# morseSounder.net
KiCad netlist of a schematic drawn in EAGLE
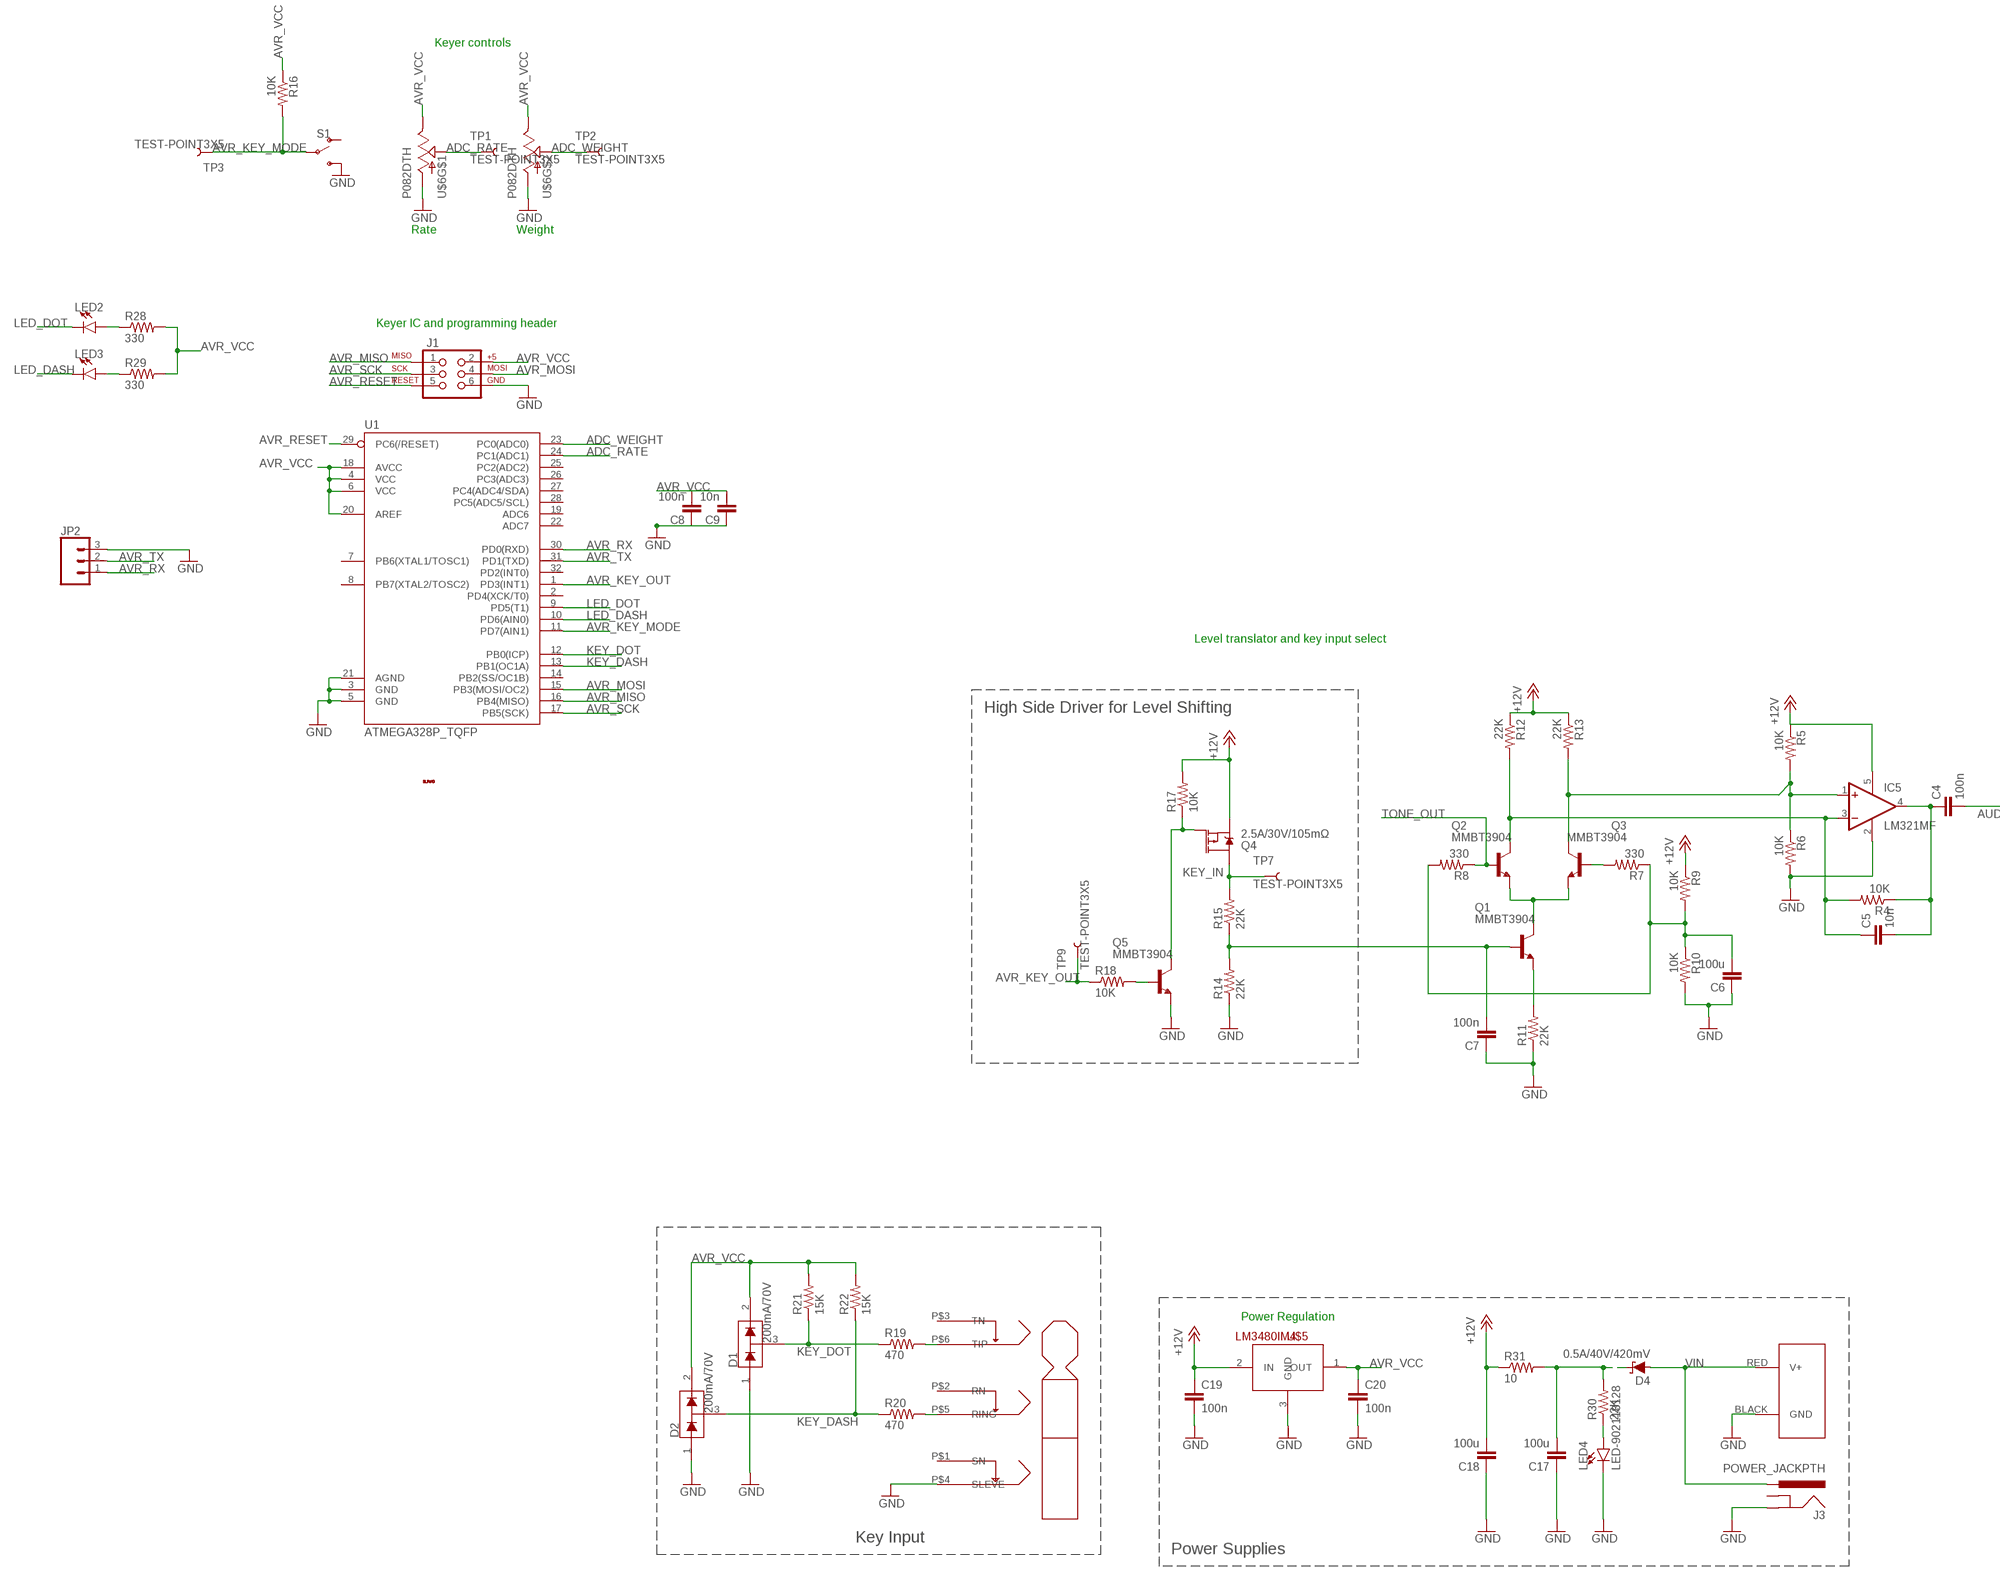
[diagram p0: schematic, sheet 1, part 1 of 2]
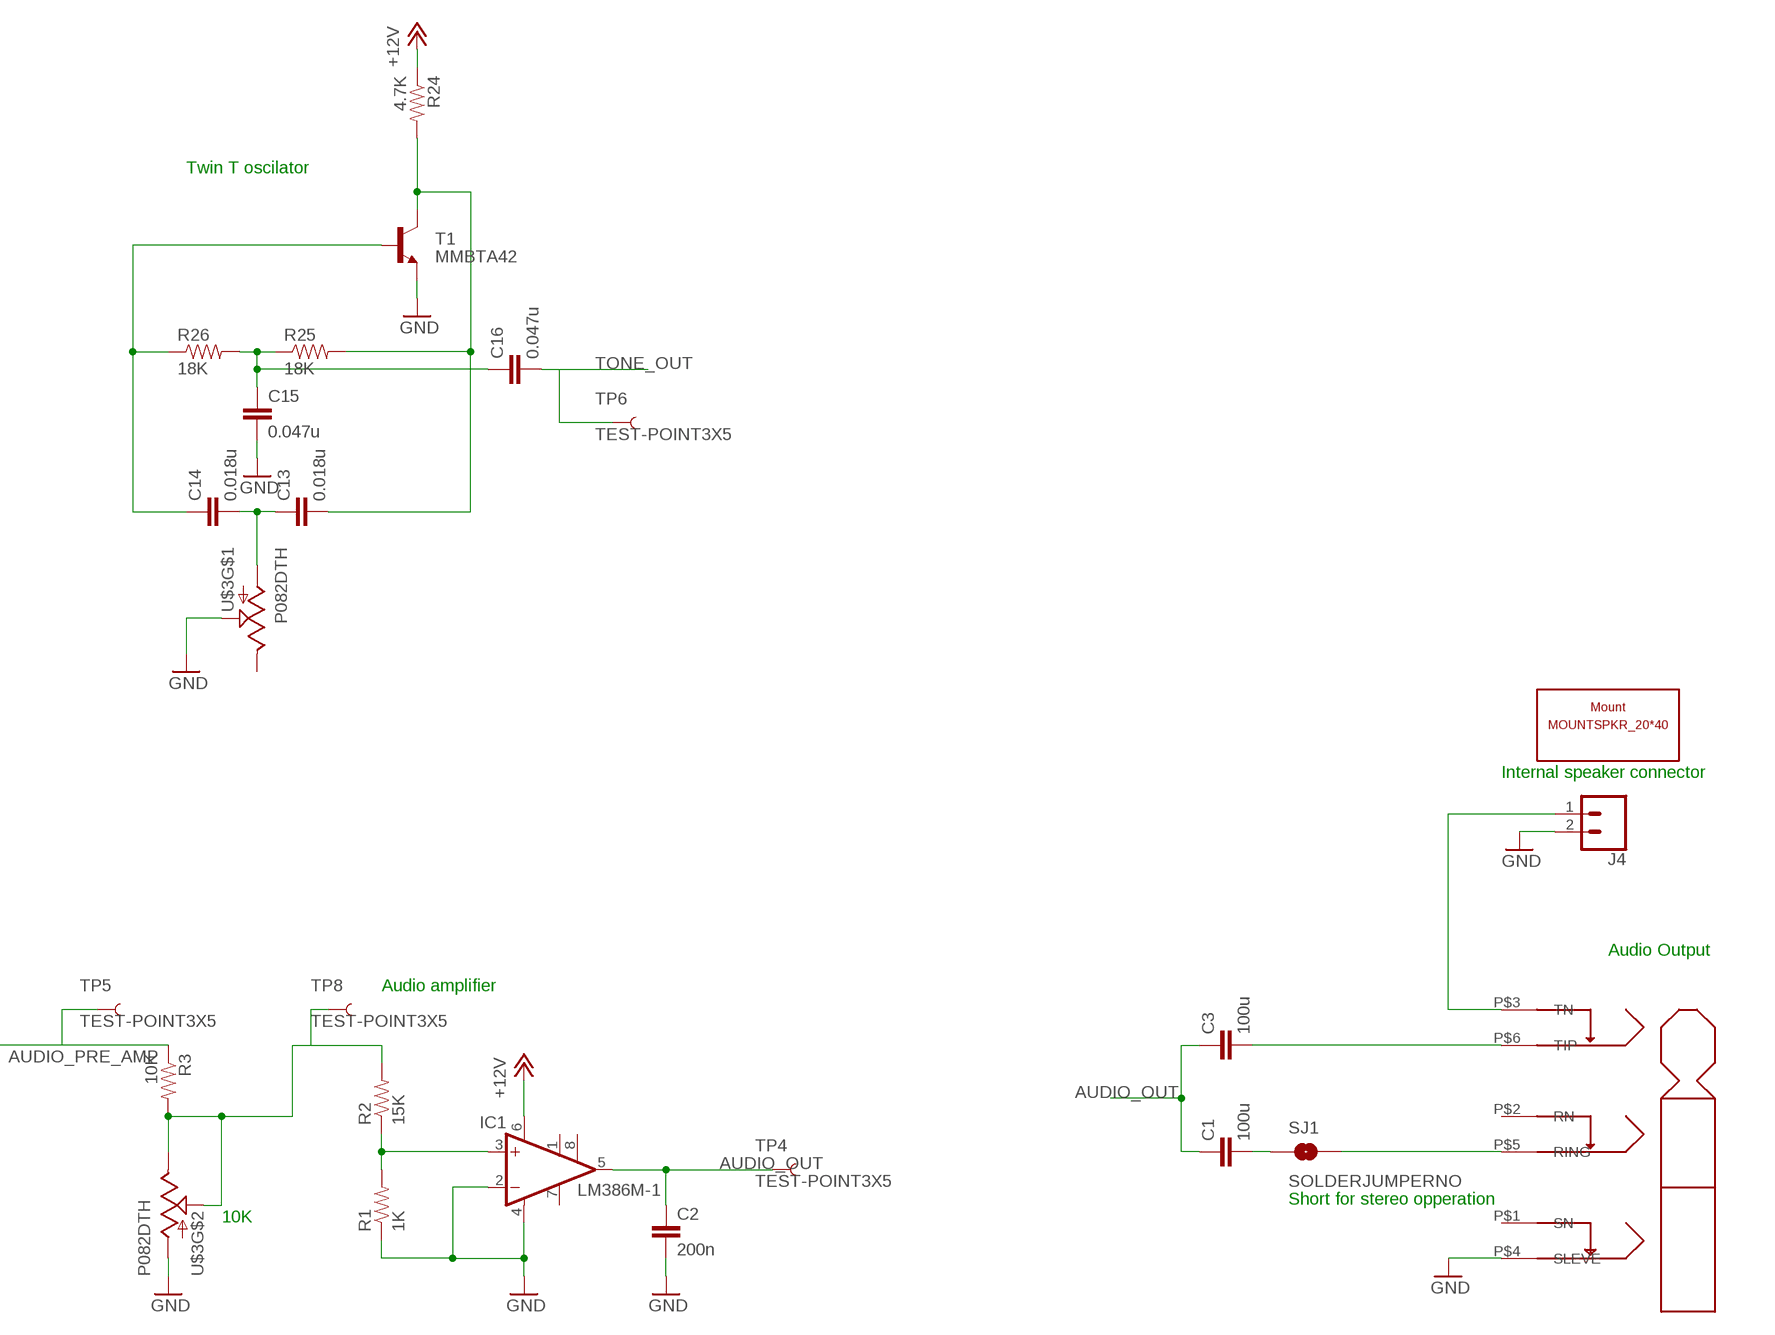
[diagram p1: schematic, sheet 1, part 2 of 2]

(export (version "E")
  (design (tool "Eeschema 10.0.6"))
  (components
    (comp (ref "C1")
      (value "100u")
      (footprint "eagle-import:0805")
      (libsource (lib "eagle-import") (part "CAP0805"))
    )
    (comp (ref "C2")
      (value "200n")
      (footprint "eagle-import:0805")
      (libsource (lib "eagle-import") (part "CAP0805"))
    )
    (comp (ref "C3")
      (value "100u")
      (footprint "eagle-import:0805")
      (libsource (lib "eagle-import") (part "CAP0805"))
    )
    (comp (ref "C4")
      (value "100n")
      (footprint "eagle-import:0805")
      (libsource (lib "eagle-import") (part "CAP0805"))
    )
    (comp (ref "C5")
      (value "10n")
      (footprint "eagle-import:0805")
      (libsource (lib "eagle-import") (part "CAP0805"))
    )
    (comp (ref "C6")
      (value "100u")
      (footprint "eagle-import:0805")
      (libsource (lib "eagle-import") (part "CAP0805"))
    )
    (comp (ref "C7")
      (value "100n")
      (footprint "eagle-import:0805")
      (libsource (lib "eagle-import") (part "CAP0805"))
    )
    (comp (ref "C8")
      (value "100n")
      (footprint "eagle-import:0805")
      (libsource (lib "eagle-import") (part "CAP0805"))
    )
    (comp (ref "C9")
      (value "10n")
      (footprint "eagle-import:0805")
      (libsource (lib "eagle-import") (part "CAP0805"))
    )
    (comp (ref "C13")
      (value "0.018u")
      (footprint "eagle-import:0805")
      (libsource (lib "eagle-import") (part "CAP0805"))
    )
    (comp (ref "C14")
      (value "0.018u")
      (footprint "eagle-import:0805")
      (libsource (lib "eagle-import") (part "CAP0805"))
    )
    (comp (ref "C15")
      (value "0.047u")
      (footprint "eagle-import:0805")
      (libsource (lib "eagle-import") (part "CAP0805"))
    )
    (comp (ref "C16")
      (value "0.047u")
      (footprint "eagle-import:0805")
      (libsource (lib "eagle-import") (part "CAP0805"))
    )
    (comp (ref "C17")
      (value "100u")
      (footprint "eagle-import:0805")
      (libsource (lib "eagle-import") (part "CAP0805"))
    )
    (comp (ref "C18")
      (value "100u")
      (footprint "eagle-import:0805")
      (libsource (lib "eagle-import") (part "CAP0805"))
    )
    (comp (ref "C19")
      (value "100n")
      (footprint "eagle-import:0805")
      (libsource (lib "eagle-import") (part "CAP0805"))
    )
    (comp (ref "C20")
      (value "100n")
      (footprint "eagle-import:0805")
      (libsource (lib "eagle-import") (part "CAP0805"))
    )
    (comp (ref "D1")
      (value "200mA/70V")
      (footprint "eagle-import:SOT23-3")
      (libsource (lib "eagle-import") (part "BAV99"))
    )
    (comp (ref "D2")
      (value "200mA/70V")
      (footprint "eagle-import:SOT23-3")
      (libsource (lib "eagle-import") (part "BAV99"))
    )
    (comp (ref "D4")
      (value "0.5A/40V/420mV")
      (footprint "eagle-import:SOD-323")
      (libsource (lib "eagle-import") (part "DIODE-SCHOTTKY-PMEG4005EJ"))
    )
    (comp (ref "IC1")
      (value "LM386M-1")
      (footprint "eagle-import:SO08")
      (libsource (lib "eagle-import") (part "LM386?-M1"))
    )
    (comp (ref "IC5")
      (value "LM321MF")
      (footprint "eagle-import:SOT23-5")
      (libsource (lib "eagle-import") (part "LM321?MF"))
    )
    (comp (ref "J1")
      (value "AVR_SPI_PRG_6PTH")
      (footprint "eagle-import:2X3")
      (libsource (lib "eagle-import") (part "AVR_SPI_PRG_6PTH"))
    )
    (comp (ref "J2")
      (value "POWERPOLE_POWER25A_HORIZONTAL_G2")
      (footprint "eagle-import:POWERPOLE_PAIR_25A_HORIZ_G2")
      (libsource (lib "eagle-import") (part "POWERPOLE_POWER25A_HORIZONTAL_G2"))
    )
    (comp (ref "J3")
      (value "POWER_JACKPTH")
      (footprint "eagle-import:POWER_JACK_PTH")
      (libsource (lib "eagle-import") (part "POWER_JACKPTH"))
    )
    (comp (ref "J4")
      (value "CONN_02")
      (footprint "eagle-import:1X02")
      (libsource (lib "eagle-import") (part "CONN_02"))
    )
    (comp (ref "JP2")
      (value "CONN_03")
      (footprint "eagle-import:1X03")
      (libsource (lib "eagle-import") (part "CONN_03"))
    )
    (comp (ref "LED2")
      (value "LED-RED1206")
      (footprint "eagle-import:LED-1206")
      (libsource (lib "eagle-import") (part "LED-RED1206"))
    )
    (comp (ref "LED3")
      (value "LED-RED1206")
      (footprint "eagle-import:LED-1206")
      (libsource (lib "eagle-import") (part "LED-RED1206"))
    )
    (comp (ref "LED4")
      (value "LED-902118128")
      (footprint "eagle-import:MULTICOMP-2118128")
      (libsource (lib "eagle-import") (part "LED-902118128"))
    )
    (comp (ref "Q1")
      (value "MMBT3904")
      (footprint "eagle-import:SOT23-BEC")
      (libsource (lib "eagle-import") (part "-NPN-SOT23-BECMMBT3904LT1"))
    )
    (comp (ref "Q2")
      (value "MMBT3904")
      (footprint "eagle-import:SOT23-BEC")
      (libsource (lib "eagle-import") (part "-NPN-SOT23-BECMMBT3904LT1"))
    )
    (comp (ref "Q3")
      (value "MMBT3904")
      (footprint "eagle-import:SOT23-BEC")
      (libsource (lib "eagle-import") (part "-NPN-SOT23-BECMMBT3904LT1"))
    )
    (comp (ref "Q4")
      (value "2.5A/30V/105mΩ")
      (footprint "eagle-import:SOT23-3")
      (libsource (lib "eagle-import") (part "MOSFET_PCH-DMG2307L"))
    )
    (comp (ref "Q5")
      (value "MMBT3904")
      (footprint "eagle-import:SOT23-BEC")
      (libsource (lib "eagle-import") (part "-NPN-SOT23-BECMMBT3904LT1"))
    )
    (comp (ref "R1")
      (value "1K")
      (footprint "eagle-import:0805")
      (libsource (lib "eagle-import") (part "RESISTOR0805-RES"))
    )
    (comp (ref "R2")
      (value "15K")
      (footprint "eagle-import:0805")
      (libsource (lib "eagle-import") (part "RESISTOR0805-RES"))
    )
    (comp (ref "R3")
      (value "10K")
      (footprint "eagle-import:0805")
      (libsource (lib "eagle-import") (part "RESISTOR0805-RES"))
    )
    (comp (ref "R4")
      (value "10K")
      (footprint "eagle-import:0805")
      (libsource (lib "eagle-import") (part "RESISTOR0805-RES"))
    )
    (comp (ref "R5")
      (value "10K")
      (footprint "eagle-import:0805")
      (libsource (lib "eagle-import") (part "RESISTOR0805-RES"))
    )
    (comp (ref "R6")
      (value "10K")
      (footprint "eagle-import:0805")
      (libsource (lib "eagle-import") (part "RESISTOR0805-RES"))
    )
    (comp (ref "R7")
      (value "330")
      (footprint "eagle-import:0805")
      (libsource (lib "eagle-import") (part "RESISTOR0805-RES"))
    )
    (comp (ref "R8")
      (value "330")
      (footprint "eagle-import:0805")
      (libsource (lib "eagle-import") (part "RESISTOR0805-RES"))
    )
    (comp (ref "R9")
      (value "10K")
      (footprint "eagle-import:0805")
      (libsource (lib "eagle-import") (part "RESISTOR0805-RES"))
    )
    (comp (ref "R10")
      (value "10K")
      (footprint "eagle-import:0805")
      (libsource (lib "eagle-import") (part "RESISTOR0805-RES"))
    )
    (comp (ref "R11")
      (value "22K")
      (footprint "eagle-import:0805")
      (libsource (lib "eagle-import") (part "RESISTOR0805-RES"))
    )
    (comp (ref "R12")
      (value "22K")
      (footprint "eagle-import:0805")
      (libsource (lib "eagle-import") (part "RESISTOR0805-RES"))
    )
    (comp (ref "R13")
      (value "22K")
      (footprint "eagle-import:0805")
      (libsource (lib "eagle-import") (part "RESISTOR0805-RES"))
    )
    (comp (ref "R14")
      (value "22K")
      (footprint "eagle-import:0805")
      (libsource (lib "eagle-import") (part "RESISTOR0805-RES"))
    )
    (comp (ref "R15")
      (value "22K")
      (footprint "eagle-import:0805")
      (libsource (lib "eagle-import") (part "RESISTOR0805-RES"))
    )
    (comp (ref "R16")
      (value "10K")
      (footprint "eagle-import:0805")
      (libsource (lib "eagle-import") (part "RESISTOR0805-RES"))
    )
    (comp (ref "R17")
      (value "10K")
      (footprint "eagle-import:0805")
      (libsource (lib "eagle-import") (part "RESISTOR0805-RES"))
    )
    (comp (ref "R18")
      (value "10K")
      (footprint "eagle-import:0805")
      (libsource (lib "eagle-import") (part "RESISTOR0805-RES"))
    )
    (comp (ref "R19")
      (value "470")
      (footprint "eagle-import:0805")
      (libsource (lib "eagle-import") (part "RESISTOR0805-RES"))
    )
    (comp (ref "R20")
      (value "470")
      (footprint "eagle-import:0805")
      (libsource (lib "eagle-import") (part "RESISTOR0805-RES"))
    )
    (comp (ref "R21")
      (value "15K")
      (footprint "eagle-import:0805")
      (libsource (lib "eagle-import") (part "RESISTOR0805-RES"))
    )
    (comp (ref "R22")
      (value "15K")
      (footprint "eagle-import:0805")
      (libsource (lib "eagle-import") (part "RESISTOR0805-RES"))
    )
    (comp (ref "R24")
      (value "4.7K")
      (footprint "eagle-import:0805")
      (libsource (lib "eagle-import") (part "RESISTOR0805-RES"))
    )
    (comp (ref "R25")
      (value "18K")
      (footprint "eagle-import:0805")
      (libsource (lib "eagle-import") (part "RESISTOR0805-RES"))
    )
    (comp (ref "R26")
      (value "18K")
      (footprint "eagle-import:0805")
      (libsource (lib "eagle-import") (part "RESISTOR0805-RES"))
    )
    (comp (ref "R28")
      (value "330")
      (footprint "eagle-import:0805")
      (libsource (lib "eagle-import") (part "RESISTOR0805-RES"))
    )
    (comp (ref "R29")
      (value "330")
      (footprint "eagle-import:0805")
      (libsource (lib "eagle-import") (part "RESISTOR0805-RES"))
    )
    (comp (ref "R30")
      (value "22K")
      (footprint "eagle-import:0805")
      (libsource (lib "eagle-import") (part "RESISTOR0805-RES"))
    )
    (comp (ref "R31")
      (value "10")
      (footprint "eagle-import:0805")
      (libsource (lib "eagle-import") (part "RESISTOR0805-RES"))
    )
    (comp (ref "S1")
      (value "SWITCH-SPDTTE-1825232-1")
      (footprint "eagle-import:TE-1825232-1")
      (libsource (lib "eagle-import") (part "SWITCH-SPDTTE-1825232-1"))
    )
    (comp (ref "SJ1")
      (value "SOLDERJUMPERNO")
      (footprint "eagle-import:SJ_2S-NO")
      (libsource (lib "eagle-import") (part "SOLDERJUMPERNO"))
    )
    (comp (ref "T1")
      (value "MMBTA42")
      (footprint "eagle-import:SOT23")
      (libsource (lib "eagle-import") (part "TRANSISTOR_NPNSOT23"))
    )
    (comp (ref "TP1")
      (value "TEST-POINT3X5")
      (footprint "eagle-import:PAD.03X.05")
      (libsource (lib "eagle-import") (part "TEST-POINT3X5"))
    )
    (comp (ref "TP2")
      (value "TEST-POINT3X5")
      (footprint "eagle-import:PAD.03X.05")
      (libsource (lib "eagle-import") (part "TEST-POINT3X5"))
    )
    (comp (ref "TP3")
      (value "TEST-POINT3X5")
      (footprint "eagle-import:PAD.03X.05")
      (libsource (lib "eagle-import") (part "TEST-POINT3X5"))
    )
    (comp (ref "TP4")
      (value "TEST-POINT3X5")
      (footprint "eagle-import:PAD.03X.05")
      (libsource (lib "eagle-import") (part "TEST-POINT3X5"))
    )
    (comp (ref "TP5")
      (value "TEST-POINT3X5")
      (footprint "eagle-import:PAD.03X.05")
      (libsource (lib "eagle-import") (part "TEST-POINT3X5"))
    )
    (comp (ref "TP6")
      (value "TEST-POINT3X5")
      (footprint "eagle-import:PAD.03X.05")
      (libsource (lib "eagle-import") (part "TEST-POINT3X5"))
    )
    (comp (ref "TP7")
      (value "TEST-POINT3X5")
      (footprint "eagle-import:PAD.03X.05")
      (libsource (lib "eagle-import") (part "TEST-POINT3X5"))
    )
    (comp (ref "TP8")
      (value "TEST-POINT3X5")
      (footprint "eagle-import:PAD.03X.05")
      (libsource (lib "eagle-import") (part "TEST-POINT3X5"))
    )
    (comp (ref "TP9")
      (value "TEST-POINT3X5")
      (footprint "eagle-import:PAD.03X.05")
      (libsource (lib "eagle-import") (part "TEST-POINT3X5"))
    )
    (comp (ref "U$1")
      (value "NRJ6HH")
      (footprint "eagle-import:NRJ6HH")
      (libsource (lib "eagle-import") (part "NRJ6HH"))
    )
    (comp (ref "U$2")
      (value "NRJ6HH")
      (footprint "eagle-import:NRJ6HH")
      (libsource (lib "eagle-import") (part "NRJ6HH"))
    )
    (comp (ref "U$3")
      (value "P082DTH")
      (footprint "eagle-import:P082D")
      (libsource (lib "eagle-import") (part "P082DTH"))
    )
    (comp (ref "U$4")
      (value "MOUNTSPKR_20*40")
      (footprint "eagle-import:SKR_MNT")
      (libsource (lib "eagle-import") (part "MOUNTSPKR_2040"))
    )
    (comp (ref "U$5")
      (value "LM3480IM4")
      (footprint "eagle-import:SOT23-3")
      (libsource (lib "eagle-import") (part "LM3480IM4"))
    )
    (comp (ref "U$6")
      (value "P082DTH")
      (footprint "eagle-import:P082D")
      (libsource (lib "eagle-import") (part "P082DTH"))
    )
    (comp (ref "U$7")
      (value "LOGO_SUWSLOGO_LARGE")
      (footprint "eagle-import:LOGO_SUWS")
      (libsource (lib "eagle-import") (part "LOGO_SUWSLOGO_LARGE"))
    )
    (comp (ref "U1")
      (value "ATMEGA328P_TQFP")
      (footprint "eagle-import:TQFP32-08")
      (libsource (lib "eagle-import") (part "ATMEGA328P_TQFP"))
    )
  )
  (nets
    (net (code "1") (name "+12V") (class "Default")
      (node (ref "C18") (pin "2") (pinfunction "2_2") (pintype "passive"))
      (node (ref "C19") (pin "1") (pinfunction "1_1") (pintype "passive"))
      (node (ref "IC1") (pin "6") (pinfunction "VS_6") (pintype "power_in"))
      (node (ref "IC5") (pin "5") (pinfunction "V+_5") (pintype "power_in"))
      (node (ref "Q4") (pin "2") (pinfunction "S_2") (pintype "bidirectional"))
      (node (ref "R12") (pin "1") (pinfunction "1_1") (pintype "passive"))
      (node (ref "R13") (pin "1") (pinfunction "1_1") (pintype "passive"))
      (node (ref "R17") (pin "2") (pinfunction "2_2") (pintype "passive"))
      (node (ref "R24") (pin "1") (pinfunction "1_1") (pintype "passive"))
      (node (ref "R31") (pin "1") (pinfunction "1_1") (pintype "passive"))
      (node (ref "R5") (pin "1") (pinfunction "1_1") (pintype "passive"))
      (node (ref "R9") (pin "1") (pinfunction "1_1") (pintype "passive"))
      (node (ref "U$5") (pin "2") (pinfunction "IN_2") (pintype "bidirectional"))
    )
    (net (code "2") (name "/ADC_RATE") (class "Default")
      (node (ref "TP1") (pin "P$1") (pinfunction "1_P$1") (pintype "bidirectional"))
      (node (ref "U$6") (pin "F2") (pinfunction "S_F2") (pintype "passive"))
      (node (ref "U1") (pin "24") (pinfunction "PC1(ADC1)_24") (pintype "bidirectional"))
    )
    (net (code "3") (name "/ADC_WEIGHT") (class "Default")
      (node (ref "TP2") (pin "P$1") (pinfunction "1_P$1") (pintype "bidirectional"))
      (node (ref "U$6") (pin "R2") (pinfunction "S_R2") (pintype "passive"))
      (node (ref "U1") (pin "23") (pinfunction "PC0(ADC0)_23") (pintype "bidirectional"))
    )
    (net (code "4") (name "/AUDIO_OUT") (class "Default")
      (node (ref "C1") (pin "1") (pinfunction "1_1") (pintype "passive"))
      (node (ref "C2") (pin "1") (pinfunction "1_1") (pintype "passive"))
      (node (ref "C3") (pin "1") (pinfunction "1_1") (pintype "passive"))
      (node (ref "IC1") (pin "5") (pinfunction "OUT_5") (pintype "output"))
      (node (ref "TP4") (pin "P$1") (pinfunction "1_P$1") (pintype "bidirectional"))
    )
    (net (code "5") (name "/AUDIO_PRE_AMP") (class "Default")
      (node (ref "C4") (pin "2") (pinfunction "2_2") (pintype "passive"))
      (node (ref "R3") (pin "1") (pinfunction "1_1") (pintype "passive"))
      (node (ref "TP5") (pin "P$1") (pinfunction "1_P$1") (pintype "bidirectional"))
    )
    (net (code "6") (name "/AVR_KEY_MODE") (class "Default")
      (node (ref "R16") (pin "2") (pinfunction "2_2") (pintype "passive"))
      (node (ref "S1") (pin "2") (pinfunction "P_2") (pintype "passive"))
      (node (ref "TP3") (pin "P$1") (pinfunction "1_P$1") (pintype "bidirectional"))
      (node (ref "U1") (pin "11") (pinfunction "PD7(AIN1)_11") (pintype "bidirectional"))
    )
    (net (code "7") (name "/AVR_KEY_OUT") (class "Default")
      (node (ref "R18") (pin "1") (pinfunction "1_1") (pintype "passive"))
      (node (ref "TP9") (pin "P$1") (pinfunction "1_P$1") (pintype "bidirectional"))
      (node (ref "U1") (pin "1") (pinfunction "PD3(INT1)_1") (pintype "bidirectional"))
    )
    (net (code "8") (name "/AVR_MISO") (class "Default")
      (node (ref "J1") (pin "1") (pinfunction "1_1") (pintype "passive"))
      (node (ref "U1") (pin "16") (pinfunction "PB4(MISO)_16") (pintype "bidirectional"))
    )
    (net (code "9") (name "/AVR_MOSI") (class "Default")
      (node (ref "J1") (pin "4") (pinfunction "4_4") (pintype "passive"))
      (node (ref "U1") (pin "15") (pinfunction "PB3(MOSI/OC2)_15") (pintype "bidirectional"))
    )
    (net (code "10") (name "/AVR_RESET") (class "Default")
      (node (ref "J1") (pin "5") (pinfunction "5_5") (pintype "passive"))
      (node (ref "U1") (pin "29") (pinfunction "PC6(/RESET)_29") (pintype "bidirectional"))
    )
    (net (code "11") (name "/AVR_RX") (class "Default")
      (node (ref "JP2") (pin "1") (pinfunction "1_1") (pintype "passive"))
      (node (ref "U1") (pin "30") (pinfunction "PD0(RXD)_30") (pintype "bidirectional"))
    )
    (net (code "12") (name "/AVR_SCK") (class "Default")
      (node (ref "J1") (pin "3") (pinfunction "3_3") (pintype "passive"))
      (node (ref "U1") (pin "17") (pinfunction "PB5(SCK)_17") (pintype "bidirectional"))
    )
    (net (code "13") (name "/AVR_TX") (class "Default")
      (node (ref "JP2") (pin "2") (pinfunction "2_2") (pintype "passive"))
      (node (ref "U1") (pin "31") (pinfunction "PD1(TXD)_31") (pintype "bidirectional"))
    )
    (net (code "14") (name "/AVR_VCC") (class "Default")
      (node (ref "C20") (pin "1") (pinfunction "1_1") (pintype "passive"))
      (node (ref "C8") (pin "2") (pinfunction "2_2") (pintype "passive"))
      (node (ref "C9") (pin "2") (pinfunction "2_2") (pintype "passive"))
      (node (ref "D1") (pin "2") (pinfunction "C2_2") (pintype "bidirectional"))
      (node (ref "D2") (pin "2") (pinfunction "C2_2") (pintype "bidirectional"))
      (node (ref "J1") (pin "2") (pinfunction "2_2") (pintype "passive"))
      (node (ref "R16") (pin "1") (pinfunction "1_1") (pintype "passive"))
      (node (ref "R21") (pin "2") (pinfunction "2_2") (pintype "passive"))
      (node (ref "R22") (pin "2") (pinfunction "2_2") (pintype "passive"))
      (node (ref "R28") (pin "2") (pinfunction "2_2") (pintype "passive"))
      (node (ref "R29") (pin "2") (pinfunction "2_2") (pintype "passive"))
      (node (ref "U$5") (pin "1") (pinfunction "OUT_1") (pintype "bidirectional"))
      (node (ref "U$6") (pin "F3") (pinfunction "E_F3") (pintype "passive"))
      (node (ref "U$6") (pin "R3") (pinfunction "E_R3") (pintype "passive"))
      (node (ref "U1") (pin "18") (pinfunction "AVCC_18") (pintype "bidirectional"))
      (node (ref "U1") (pin "20") (pinfunction "AREF_20") (pintype "bidirectional"))
      (node (ref "U1") (pin "4") (pinfunction "VCC_4") (pintype "bidirectional"))
      (node (ref "U1") (pin "6") (pinfunction "VCC_6") (pintype "bidirectional"))
    )
    (net (code "15") (name "/KEY_DASH") (class "Default")
      (node (ref "D2") (pin "3") (pinfunction "COM_3") (pintype "bidirectional"))
      (node (ref "R20") (pin "1") (pinfunction "1_1") (pintype "passive"))
      (node (ref "R22") (pin "1") (pinfunction "1_1") (pintype "passive"))
      (node (ref "U1") (pin "13") (pinfunction "PB1(OC1A)_13") (pintype "bidirectional"))
    )
    (net (code "16") (name "/KEY_DOT") (class "Default")
      (node (ref "D1") (pin "3") (pinfunction "COM_3") (pintype "bidirectional"))
      (node (ref "R19") (pin "1") (pinfunction "1_1") (pintype "passive"))
      (node (ref "R21") (pin "1") (pinfunction "1_1") (pintype "passive"))
      (node (ref "U1") (pin "12") (pinfunction "PB0(ICP)_12") (pintype "bidirectional"))
    )
    (net (code "17") (name "/KEY_IN") (class "Default")
      (node (ref "Q4") (pin "3") (pinfunction "D_3") (pintype "bidirectional"))
      (node (ref "R15") (pin "2") (pinfunction "2_2") (pintype "passive"))
      (node (ref "TP7") (pin "P$1") (pinfunction "1_P$1") (pintype "bidirectional"))
    )
    (net (code "18") (name "/LED_DASH") (class "Default")
      (node (ref "LED3") (pin "C") (pinfunction "C_C") (pintype "passive"))
      (node (ref "U1") (pin "10") (pinfunction "PD6(AIN0)_10") (pintype "bidirectional"))
    )
    (net (code "19") (name "/LED_DOT") (class "Default")
      (node (ref "LED2") (pin "C") (pinfunction "C_C") (pintype "passive"))
      (node (ref "U1") (pin "9") (pinfunction "PD5(T1)_9") (pintype "bidirectional"))
    )
    (net (code "20") (name "/TONE_OUT") (class "Default")
      (node (ref "C16") (pin "2") (pinfunction "2_2") (pintype "passive"))
      (node (ref "Q2") (pin "B") (pinfunction "B_B") (pintype "passive"))
      (node (ref "R8") (pin "1") (pinfunction "1_1") (pintype "passive"))
      (node (ref "TP6") (pin "P$1") (pinfunction "1_P$1") (pintype "bidirectional"))
    )
    (net (code "21") (name "/VIN") (class "Default")
      (node (ref "D4") (pin "A") (pinfunction "A_A") (pintype "passive"))
      (node (ref "J2") (pin "RED") (pinfunction "V+_RED") (pintype "power_in"))
      (node (ref "J3") (pin "PWR") (pinfunction "PWR_PWR") (pintype "bidirectional"))
    )
    (net (code "22") (name "GND") (class "Default")
      (node (ref "C15") (pin "2") (pinfunction "2_2") (pintype "passive"))
      (node (ref "C17") (pin "1") (pinfunction "1_1") (pintype "passive"))
      (node (ref "C18") (pin "1") (pinfunction "1_1") (pintype "passive"))
      (node (ref "C19") (pin "2") (pinfunction "2_2") (pintype "passive"))
      (node (ref "C2") (pin "2") (pinfunction "2_2") (pintype "passive"))
      (node (ref "C20") (pin "2") (pinfunction "2_2") (pintype "passive"))
      (node (ref "C6") (pin "1") (pinfunction "1_1") (pintype "passive"))
      (node (ref "C7") (pin "1") (pinfunction "1_1") (pintype "passive"))
      (node (ref "C8") (pin "1") (pinfunction "1_1") (pintype "passive"))
      (node (ref "C9") (pin "1") (pinfunction "1_1") (pintype "passive"))
      (node (ref "D1") (pin "1") (pinfunction "A1_1") (pintype "bidirectional"))
      (node (ref "D2") (pin "1") (pinfunction "A1_1") (pintype "bidirectional"))
      (node (ref "IC1") (pin "2") (pinfunction "-IN_2") (pintype "input"))
      (node (ref "IC1") (pin "4") (pinfunction "GND_4") (pintype "power_in"))
      (node (ref "IC5") (pin "2") (pinfunction "V-_2") (pintype "power_in"))
      (node (ref "J1") (pin "6") (pinfunction "6_6") (pintype "passive"))
      (node (ref "J2") (pin "BLACK") (pinfunction "GND_BLACK") (pintype "power_in"))
      (node (ref "J3") (pin "GND") (pinfunction "GND_GND") (pintype "bidirectional"))
      (node (ref "J4") (pin "2") (pinfunction "2_2") (pintype "passive"))
      (node (ref "JP2") (pin "3") (pinfunction "3_3") (pintype "passive"))
      (node (ref "LED4") (pin "P$2") (pinfunction "C_P$2") (pintype "passive"))
      (node (ref "Q5") (pin "E") (pinfunction "E_E") (pintype "passive"))
      (node (ref "R1") (pin "1") (pinfunction "1_1") (pintype "passive"))
      (node (ref "R10") (pin "2") (pinfunction "2_2") (pintype "passive"))
      (node (ref "R11") (pin "1") (pinfunction "1_1") (pintype "passive"))
      (node (ref "R14") (pin "1") (pinfunction "1_1") (pintype "passive"))
      (node (ref "R6") (pin "2") (pinfunction "2_2") (pintype "passive"))
      (node (ref "S1") (pin "3") (pinfunction "S_3") (pintype "passive"))
      (node (ref "T1") (pin "2") (pinfunction "E_2") (pintype "passive"))
      (node (ref "U$1") (pin "P$4") (pinfunction "SLEVE_P$4") (pintype "bidirectional"))
      (node (ref "U$2") (pin "P$4") (pinfunction "SLEVE_P$4") (pintype "bidirectional"))
      (node (ref "U$3") (pin "F2") (pinfunction "S_F2") (pintype "passive"))
      (node (ref "U$3") (pin "R1") (pinfunction "A_R1") (pintype "passive"))
      (node (ref "U$5") (pin "3") (pinfunction "GND_3") (pintype "bidirectional"))
      (node (ref "U$6") (pin "F1") (pinfunction "A_F1") (pintype "passive"))
      (node (ref "U$6") (pin "R1") (pinfunction "A_R1") (pintype "passive"))
      (node (ref "U1") (pin "21") (pinfunction "AGND_21") (pintype "bidirectional"))
      (node (ref "U1") (pin "3") (pinfunction "GND_3") (pintype "bidirectional"))
      (node (ref "U1") (pin "5") (pinfunction "GND_5") (pintype "bidirectional"))
    )
    (net (code "23") (name "Net-(C1-Pad2)") (class "Default")
      (node (ref "C1") (pin "2") (pinfunction "2_2") (pintype "passive"))
      (node (ref "SJ1") (pin "1") (pinfunction "1_1") (pintype "passive"))
    )
    (net (code "24") (name "Net-(C6-Pad2)") (class "Default")
      (node (ref "C6") (pin "2") (pinfunction "2_2") (pintype "passive"))
      (node (ref "R10") (pin "1") (pinfunction "1_1") (pintype "passive"))
      (node (ref "R7") (pin "1") (pinfunction "1_1") (pintype "passive"))
      (node (ref "R8") (pin "2") (pinfunction "2_2") (pintype "passive"))
      (node (ref "R9") (pin "2") (pinfunction "2_2") (pintype "passive"))
    )
    (net (code "25") (name "Net-(C7-Pad2)") (class "Default")
      (node (ref "C7") (pin "2") (pinfunction "2_2") (pintype "passive"))
      (node (ref "Q1") (pin "B") (pinfunction "B_B") (pintype "passive"))
      (node (ref "R14") (pin "2") (pinfunction "2_2") (pintype "passive"))
      (node (ref "R15") (pin "1") (pinfunction "1_1") (pintype "passive"))
    )
    (net (code "26") (name "Net-(C15-Pad1)") (class "Default")
      (node (ref "C15") (pin "1") (pinfunction "1_1") (pintype "passive"))
      (node (ref "C16") (pin "1") (pinfunction "1_1") (pintype "passive"))
      (node (ref "R25") (pin "1") (pinfunction "1_1") (pintype "passive"))
      (node (ref "R26") (pin "2") (pinfunction "2_2") (pintype "passive"))
    )
    (net (code "27") (name "Net-(C17-Pad2)") (class "Default")
      (node (ref "C17") (pin "2") (pinfunction "2_2") (pintype "passive"))
      (node (ref "D4") (pin "C") (pinfunction "C_C") (pintype "passive"))
      (node (ref "R30") (pin "2") (pinfunction "2_2") (pintype "passive"))
      (node (ref "R31") (pin "2") (pinfunction "2_2") (pintype "passive"))
    )
    (net (code "28") (name "Net-(IC1-+IN)") (class "Default")
      (node (ref "IC1") (pin "3") (pinfunction "+IN_3") (pintype "input"))
      (node (ref "R1") (pin "2") (pinfunction "2_2") (pintype "passive"))
      (node (ref "R2") (pin "1") (pinfunction "1_1") (pintype "passive"))
    )
    (net (code "29") (name "Net-(IC5-+IN)") (class "Default")
      (node (ref "IC5") (pin "1") (pinfunction "+IN_1") (pintype "input"))
      (node (ref "Q3") (pin "C") (pinfunction "C_C") (pintype "passive"))
      (node (ref "R13") (pin "2") (pinfunction "2_2") (pintype "passive"))
      (node (ref "R5") (pin "2") (pinfunction "2_2") (pintype "passive"))
      (node (ref "R6") (pin "1") (pinfunction "1_1") (pintype "passive"))
    )
    (net (code "30") (name "Net-(IC5--IN)") (class "Default")
      (node (ref "C5") (pin "1") (pinfunction "1_1") (pintype "passive"))
      (node (ref "IC5") (pin "3") (pinfunction "-IN_3") (pintype "input"))
      (node (ref "Q2") (pin "C") (pinfunction "C_C") (pintype "passive"))
      (node (ref "R12") (pin "2") (pinfunction "2_2") (pintype "passive"))
      (node (ref "R4") (pin "2") (pinfunction "2_2") (pintype "passive"))
    )
    (net (code "31") (name "Net-(IC5-OUT)") (class "Default")
      (node (ref "C4") (pin "1") (pinfunction "1_1") (pintype "passive"))
      (node (ref "C5") (pin "2") (pinfunction "2_2") (pintype "passive"))
      (node (ref "IC5") (pin "4") (pinfunction "OUT_4") (pintype "output"))
      (node (ref "R4") (pin "1") (pinfunction "1_1") (pintype "passive"))
    )
    (net (code "32") (name "Net-(LED2-PadA)") (class "Default")
      (node (ref "LED2") (pin "A") (pinfunction "A_A") (pintype "passive"))
      (node (ref "R28") (pin "1") (pinfunction "1_1") (pintype "passive"))
    )
    (net (code "33") (name "Net-(LED3-PadA)") (class "Default")
      (node (ref "LED3") (pin "A") (pinfunction "A_A") (pintype "passive"))
      (node (ref "R29") (pin "1") (pinfunction "1_1") (pintype "passive"))
    )
    (net (code "34") (name "Net-(LED4-A)") (class "Default")
      (node (ref "LED4") (pin "P$1") (pinfunction "A_P$1") (pintype "passive"))
      (node (ref "R30") (pin "1") (pinfunction "1_1") (pintype "passive"))
    )
    (net (code "35") (name "Net-(Q1-PadC)") (class "Default")
      (node (ref "Q1") (pin "C") (pinfunction "C_C") (pintype "passive"))
      (node (ref "Q2") (pin "E") (pinfunction "E_E") (pintype "passive"))
      (node (ref "Q3") (pin "E") (pinfunction "E_E") (pintype "passive"))
    )
    (net (code "36") (name "Net-(Q1-PadE)") (class "Default")
      (node (ref "Q1") (pin "E") (pinfunction "E_E") (pintype "passive"))
      (node (ref "R11") (pin "2") (pinfunction "2_2") (pintype "passive"))
    )
    (net (code "37") (name "Net-(Q3-PadB)") (class "Default")
      (node (ref "Q3") (pin "B") (pinfunction "B_B") (pintype "passive"))
      (node (ref "R7") (pin "2") (pinfunction "2_2") (pintype "passive"))
    )
    (net (code "38") (name "Net-(Q4-G)") (class "Default")
      (node (ref "Q4") (pin "1") (pinfunction "G_1") (pintype "bidirectional"))
      (node (ref "Q5") (pin "C") (pinfunction "C_C") (pintype "passive"))
      (node (ref "R17") (pin "1") (pinfunction "1_1") (pintype "passive"))
    )
    (net (code "39") (name "Net-(Q5-PadB)") (class "Default")
      (node (ref "Q5") (pin "B") (pinfunction "B_B") (pintype "passive"))
      (node (ref "R18") (pin "2") (pinfunction "2_2") (pintype "passive"))
    )
    (net (code "40") (name "Net-(T1-B)") (class "Default")
      (node (ref "C14") (pin "1") (pinfunction "1_1") (pintype "passive"))
      (node (ref "R26") (pin "1") (pinfunction "1_1") (pintype "passive"))
      (node (ref "T1") (pin "1") (pinfunction "B_1") (pintype "passive"))
    )
    (net (code "41") (name "Net-(T1-C)") (class "Default")
      (node (ref "C13") (pin "2") (pinfunction "2_2") (pintype "passive"))
      (node (ref "R24") (pin "2") (pinfunction "2_2") (pintype "passive"))
      (node (ref "R25") (pin "2") (pinfunction "2_2") (pintype "passive"))
      (node (ref "T1") (pin "3") (pinfunction "C_3") (pintype "passive"))
    )
    (net (code "42") (name "Net-(TP8-1)") (class "Default")
      (node (ref "R2") (pin "2") (pinfunction "2_2") (pintype "passive"))
      (node (ref "R3") (pin "2") (pinfunction "2_2") (pintype "passive"))
      (node (ref "TP8") (pin "P$1") (pinfunction "1_P$1") (pintype "bidirectional"))
      (node (ref "U$3") (pin "R2") (pinfunction "S_R2") (pintype "passive"))
      (node (ref "U$3") (pin "R3") (pinfunction "E_R3") (pintype "passive"))
    )
    (net (code "43") (name "Net-(U$1-RING)") (class "Default")
      (node (ref "R20") (pin "2") (pinfunction "2_2") (pintype "passive"))
      (node (ref "U$1") (pin "P$5") (pinfunction "RING_P$5") (pintype "bidirectional"))
    )
    (net (code "44") (name "Net-(U$1-TIP)") (class "Default")
      (node (ref "R19") (pin "2") (pinfunction "2_2") (pintype "passive"))
      (node (ref "U$1") (pin "P$6") (pinfunction "TIP_P$6") (pintype "bidirectional"))
    )
    (net (code "45") (name "Net-(U$2-RING)") (class "Default")
      (node (ref "SJ1") (pin "2") (pinfunction "2_2") (pintype "passive"))
      (node (ref "U$2") (pin "P$5") (pinfunction "RING_P$5") (pintype "bidirectional"))
    )
    (net (code "46") (name "Net-(U$2-TIP)") (class "Default")
      (node (ref "C3") (pin "2") (pinfunction "2_2") (pintype "passive"))
      (node (ref "U$2") (pin "P$6") (pinfunction "TIP_P$6") (pintype "bidirectional"))
    )
    (net (code "47") (name "Net-(U$2-TN)") (class "Default")
      (node (ref "J4") (pin "1") (pinfunction "1_1") (pintype "passive"))
      (node (ref "U$2") (pin "P$3") (pinfunction "TN_P$3") (pintype "bidirectional"))
    )
    (net (code "48") (name "Net-(U$3A-A)") (class "Default")
      (node (ref "C13") (pin "1") (pinfunction "1_1") (pintype "passive"))
      (node (ref "C14") (pin "2") (pinfunction "2_2") (pintype "passive"))
      (node (ref "U$3") (pin "F1") (pinfunction "A_F1") (pintype "passive"))
    )
    (net (code "49") (name "unconnected-(IC1-BYPASS-Pad7)") (class "Default")
      (node (ref "IC1") (pin "7") (pinfunction "BYPASS_7") (pintype "passive"))
    )
    (net (code "50") (name "unconnected-(IC1-GAIN-Pad1)") (class "Default")
      (node (ref "IC1") (pin "1") (pinfunction "GAIN_1") (pintype "passive"))
    )
    (net (code "51") (name "unconnected-(IC1-GAIN-Pad8)") (class "Default")
      (node (ref "IC1") (pin "8") (pinfunction "GAIN_8") (pintype "passive"))
    )
    (net (code "52") (name "unconnected-(J3-PadGNDBREAK)") (class "Default")
      (node (ref "J3") (pin "GNDBREAK") (pinfunction "GNDBREAK_GNDBREAK") (pintype "bidirectional"))
    )
    (net (code "53") (name "unconnected-(S1-O-Pad1)") (class "Default")
      (node (ref "S1") (pin "1") (pinfunction "O_1") (pintype "passive"))
    )
    (net (code "54") (name "unconnected-(U$1-RN-PadP$2)") (class "Default")
      (node (ref "U$1") (pin "P$2") (pinfunction "RN_P$2") (pintype "bidirectional"))
    )
    (net (code "55") (name "unconnected-(U$1-SN-PadP$1)") (class "Default")
      (node (ref "U$1") (pin "P$1") (pinfunction "SN_P$1") (pintype "bidirectional"))
    )
    (net (code "56") (name "unconnected-(U$1-TN-PadP$3)") (class "Default")
      (node (ref "U$1") (pin "P$3") (pinfunction "TN_P$3") (pintype "bidirectional"))
    )
    (net (code "57") (name "unconnected-(U$2-RN-PadP$2)") (class "Default")
      (node (ref "U$2") (pin "P$2") (pinfunction "RN_P$2") (pintype "bidirectional"))
    )
    (net (code "58") (name "unconnected-(U$2-SN-PadP$1)") (class "Default")
      (node (ref "U$2") (pin "P$1") (pinfunction "SN_P$1") (pintype "bidirectional"))
    )
    (net (code "59") (name "unconnected-(U$3A-E-PadF3)") (class "Default")
      (node (ref "U$3") (pin "F3") (pinfunction "E_F3") (pintype "passive"))
    )
    (net (code "60") (name "unconnected-(U1-ADC6-Pad19)") (class "Default")
      (node (ref "U1") (pin "19") (pinfunction "ADC6_19") (pintype "bidirectional"))
    )
    (net (code "61") (name "unconnected-(U1-ADC7-Pad22)") (class "Default")
      (node (ref "U1") (pin "22") (pinfunction "ADC7_22") (pintype "bidirectional"))
    )
    (net (code "62") (name "unconnected-(U1-PB2(SS{slash}OC1B)-Pad14)") (class "Default")
      (node (ref "U1") (pin "14") (pinfunction "PB2(SS/OC1B)_14") (pintype "bidirectional"))
    )
    (net (code "63") (name "unconnected-(U1-PB6(XTAL1{slash}TOSC1)-Pad7)") (class "Default")
      (node (ref "U1") (pin "7") (pinfunction "PB6(XTAL1/TOSC1)_7") (pintype "bidirectional"))
    )
    (net (code "64") (name "unconnected-(U1-PB7(XTAL2{slash}TOSC2)-Pad8)") (class "Default")
      (node (ref "U1") (pin "8") (pinfunction "PB7(XTAL2/TOSC2)_8") (pintype "bidirectional"))
    )
    (net (code "65") (name "unconnected-(U1-PC2(ADC2)-Pad25)") (class "Default")
      (node (ref "U1") (pin "25") (pinfunction "PC2(ADC2)_25") (pintype "bidirectional"))
    )
    (net (code "66") (name "unconnected-(U1-PC3(ADC3)-Pad26)") (class "Default")
      (node (ref "U1") (pin "26") (pinfunction "PC3(ADC3)_26") (pintype "bidirectional"))
    )
    (net (code "67") (name "unconnected-(U1-PC4(ADC4{slash}SDA)-Pad27)") (class "Default")
      (node (ref "U1") (pin "27") (pinfunction "PC4(ADC4/SDA)_27") (pintype "bidirectional"))
    )
    (net (code "68") (name "unconnected-(U1-PC5(ADC5{slash}SCL)-Pad28)") (class "Default")
      (node (ref "U1") (pin "28") (pinfunction "PC5(ADC5/SCL)_28") (pintype "bidirectional"))
    )
    (net (code "69") (name "unconnected-(U1-PD2(INT0)-Pad32)") (class "Default")
      (node (ref "U1") (pin "32") (pinfunction "PD2(INT0)_32") (pintype "bidirectional"))
    )
    (net (code "70") (name "unconnected-(U1-PD4(XCK{slash}T0)-Pad2)") (class "Default")
      (node (ref "U1") (pin "2") (pinfunction "PD4(XCK/T0)_2") (pintype "bidirectional"))
    )
  )
)
